# Control.net
KiCad netlist of a schematic drawn in Altium Designer
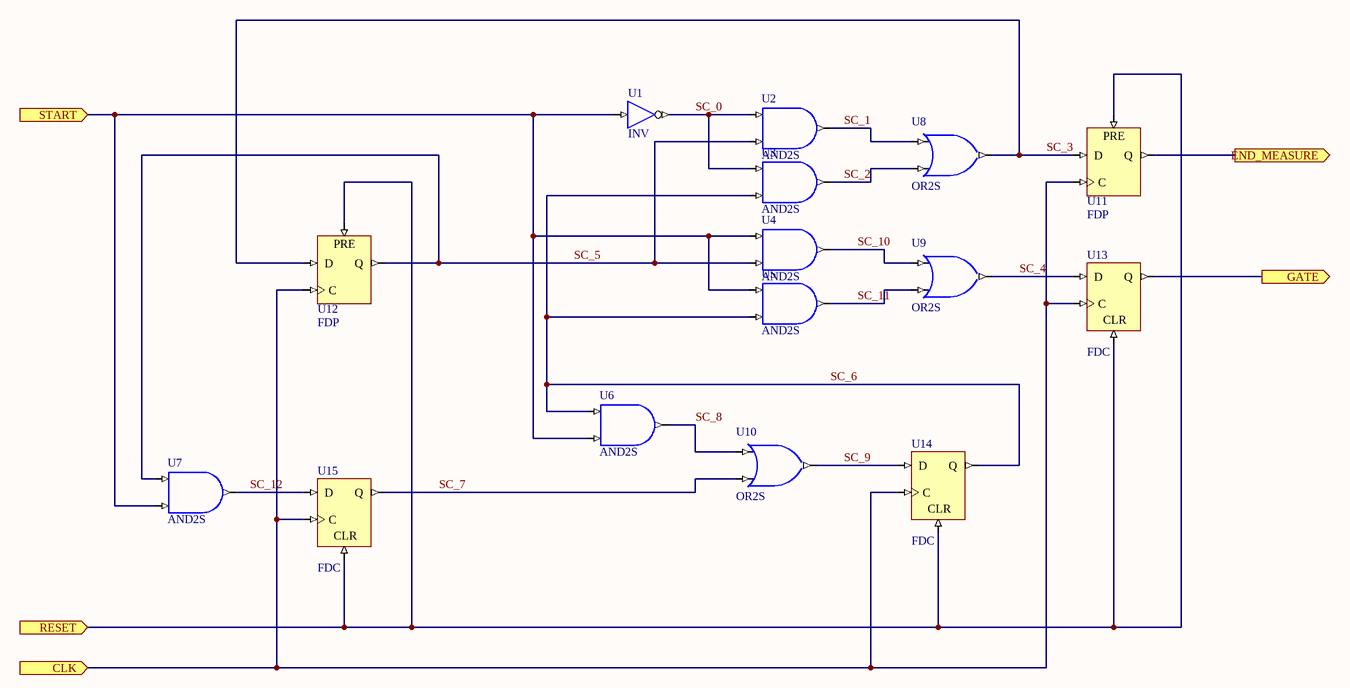
[diagram p0: Control.SchDoc]

(export (version "E")
  (design (tool "Eeschema 10.0.6"))
  (components
    (comp (ref "U1")
      (value "INV")
      (description "Inverter")
      (fields (field (name "PUBLISHER") "Altium Limited"))
      (libsource (lib "FPGA Generic") (part "INV"))
    )
    (comp (ref "U2")
      (value "AND2S")
      (description "2-Input AND Gate, Single Pin Version")
      (fields (field (name "PUBLISHER") "Altium Limited"))
      (libsource (lib "FPGA Generic") (part "AND2S"))
    )
    (comp (ref "U3")
      (value "AND2S")
      (description "2-Input AND Gate, Single Pin Version")
      (fields (field (name "PUBLISHER") "Altium Limited"))
      (libsource (lib "FPGA Generic") (part "AND2S"))
    )
    (comp (ref "U4")
      (value "AND2S")
      (description "2-Input AND Gate, Single Pin Version")
      (fields (field (name "PUBLISHER") "Altium Limited"))
      (libsource (lib "FPGA Generic") (part "AND2S"))
    )
    (comp (ref "U5")
      (value "AND2S")
      (description "2-Input AND Gate, Single Pin Version")
      (fields (field (name "PUBLISHER") "Altium Limited"))
      (libsource (lib "FPGA Generic") (part "AND2S"))
    )
    (comp (ref "U6")
      (value "AND2S")
      (description "2-Input AND Gate, Single Pin Version")
      (fields (field (name "PUBLISHER") "Altium Limited"))
      (libsource (lib "FPGA Generic") (part "AND2S"))
    )
    (comp (ref "U7")
      (value "AND2S")
      (description "2-Input AND Gate, Single Pin Version")
      (fields (field (name "PUBLISHER") "Altium Limited"))
      (libsource (lib "FPGA Generic") (part "AND2S"))
    )
    (comp (ref "U8")
      (value "OR2S")
      (description "2-Input OR Gate, Single Pin Version")
      (fields (field (name "PUBLISHER") "Altium Limited"))
      (libsource (lib "FPGA Generic") (part "OR2S"))
    )
    (comp (ref "U9")
      (value "OR2S")
      (description "2-Input OR Gate, Single Pin Version")
      (fields (field (name "PUBLISHER") "Altium Limited"))
      (libsource (lib "FPGA Generic") (part "OR2S"))
    )
    (comp (ref "U10")
      (value "OR2S")
      (description "2-Input OR Gate, Single Pin Version")
      (fields (field (name "PUBLISHER") "Altium Limited"))
      (libsource (lib "FPGA Generic") (part "OR2S"))
    )
    (comp (ref "U11")
      (value "FDP")
      (description "D-Type Flip-Flop with Asynchronous Preset")
      (fields (field (name "PUBLISHER") "Altium Limited"))
      (libsource (lib "FPGA Generic") (part "FDP"))
    )
    (comp (ref "U12")
      (value "FDP")
      (description "D-Type Flip-Flop with Asynchronous Preset")
      (fields (field (name "PUBLISHER") "Altium Limited"))
      (libsource (lib "FPGA Generic") (part "FDP"))
    )
    (comp (ref "U13")
      (value "FDC")
      (description "D-Type Flip-Flop with Asynchronous Clear")
      (fields (field (name "PUBLISHER") "Altium Limited"))
      (libsource (lib "FPGA Generic") (part "FDC"))
    )
    (comp (ref "U14")
      (value "FDC")
      (description "D-Type Flip-Flop with Asynchronous Clear")
      (fields (field (name "PUBLISHER") "Altium Limited"))
      (libsource (lib "FPGA Generic") (part "FDC"))
    )
    (comp (ref "U15")
      (value "FDC")
      (description "D-Type Flip-Flop with Asynchronous Clear")
      (fields (field (name "PUBLISHER") "Altium Limited"))
      (libsource (lib "FPGA Generic") (part "FDC"))
    )
  )
  (nets
    (net (code "1") (name "/CLK") (class "Default")
      (node (ref "U11") (pin "C") (pinfunction "C_C") (pintype "input"))
      (node (ref "U12") (pin "C") (pinfunction "C_C") (pintype "input"))
      (node (ref "U13") (pin "C") (pinfunction "C_C") (pintype "input"))
      (node (ref "U14") (pin "C") (pinfunction "C_C") (pintype "input"))
      (node (ref "U15") (pin "C") (pinfunction "C_C") (pintype "input"))
    )
    (net (code "2") (name "/END_MEASURE") (class "Default")
      (node (ref "U11") (pin "Q") (pinfunction "Q_Q") (pintype "output"))
    )
    (net (code "3") (name "/GATE") (class "Default")
      (node (ref "U13") (pin "Q") (pinfunction "Q_Q") (pintype "output"))
    )
    (net (code "4") (name "/RESET") (class "Default")
      (node (ref "U11") (pin "PRE") (pinfunction "PRE_PRE") (pintype "input"))
      (node (ref "U12") (pin "PRE") (pinfunction "PRE_PRE") (pintype "input"))
      (node (ref "U13") (pin "CLR") (pinfunction "CLR_CLR") (pintype "input"))
      (node (ref "U14") (pin "CLR") (pinfunction "CLR_CLR") (pintype "input"))
      (node (ref "U15") (pin "CLR") (pinfunction "CLR_CLR") (pintype "input"))
    )
    (net (code "5") (name "/SC_0") (class "Default")
      (node (ref "U1") (pin "O") (pinfunction "O_O") (pintype "output"))
      (node (ref "U2") (pin "I0") (pinfunction "I0_I0") (pintype "input"))
      (node (ref "U3") (pin "I0") (pinfunction "I0_I0") (pintype "input"))
    )
    (net (code "6") (name "/SC_1") (class "Default")
      (node (ref "U2") (pin "O") (pinfunction "O_O") (pintype "output"))
      (node (ref "U8") (pin "I0") (pinfunction "I0_I0") (pintype "input"))
    )
    (net (code "7") (name "/SC_2") (class "Default")
      (node (ref "U3") (pin "O") (pinfunction "O_O") (pintype "output"))
      (node (ref "U8") (pin "I1") (pinfunction "I1_I1") (pintype "input"))
    )
    (net (code "8") (name "/SC_3") (class "Default")
      (node (ref "U11") (pin "D") (pinfunction "D_D") (pintype "input"))
      (node (ref "U12") (pin "D") (pinfunction "D_D") (pintype "input"))
      (node (ref "U8") (pin "O") (pinfunction "O_O") (pintype "output"))
    )
    (net (code "9") (name "/SC_4") (class "Default")
      (node (ref "U13") (pin "D") (pinfunction "D_D") (pintype "input"))
      (node (ref "U9") (pin "O") (pinfunction "O_O") (pintype "output"))
    )
    (net (code "10") (name "/SC_5") (class "Default")
      (node (ref "U12") (pin "Q") (pinfunction "Q_Q") (pintype "output"))
      (node (ref "U2") (pin "I1") (pinfunction "I1_I1") (pintype "input"))
      (node (ref "U4") (pin "I1") (pinfunction "I1_I1") (pintype "input"))
      (node (ref "U7") (pin "I0") (pinfunction "I0_I0") (pintype "input"))
    )
    (net (code "11") (name "/SC_6") (class "Default")
      (node (ref "U14") (pin "Q") (pinfunction "Q_Q") (pintype "output"))
      (node (ref "U3") (pin "I1") (pinfunction "I1_I1") (pintype "input"))
      (node (ref "U5") (pin "I1") (pinfunction "I1_I1") (pintype "input"))
      (node (ref "U6") (pin "I0") (pinfunction "I0_I0") (pintype "input"))
    )
    (net (code "12") (name "/SC_7") (class "Default")
      (node (ref "U10") (pin "I1") (pinfunction "I1_I1") (pintype "input"))
      (node (ref "U15") (pin "Q") (pinfunction "Q_Q") (pintype "output"))
    )
    (net (code "13") (name "/SC_8") (class "Default")
      (node (ref "U10") (pin "I0") (pinfunction "I0_I0") (pintype "input"))
      (node (ref "U6") (pin "O") (pinfunction "O_O") (pintype "output"))
    )
    (net (code "14") (name "/SC_9") (class "Default")
      (node (ref "U10") (pin "O") (pinfunction "O_O") (pintype "output"))
      (node (ref "U14") (pin "D") (pinfunction "D_D") (pintype "input"))
    )
    (net (code "15") (name "/SC_10") (class "Default")
      (node (ref "U4") (pin "O") (pinfunction "O_O") (pintype "output"))
      (node (ref "U9") (pin "I0") (pinfunction "I0_I0") (pintype "input"))
    )
    (net (code "16") (name "/SC_11") (class "Default")
      (node (ref "U5") (pin "O") (pinfunction "O_O") (pintype "output"))
      (node (ref "U9") (pin "I1") (pinfunction "I1_I1") (pintype "input"))
    )
    (net (code "17") (name "/SC_12") (class "Default")
      (node (ref "U15") (pin "D") (pinfunction "D_D") (pintype "input"))
      (node (ref "U7") (pin "O") (pinfunction "O_O") (pintype "output"))
    )
    (net (code "18") (name "/START") (class "Default")
      (node (ref "U1") (pin "I") (pinfunction "I_I") (pintype "input"))
      (node (ref "U4") (pin "I0") (pinfunction "I0_I0") (pintype "input"))
      (node (ref "U5") (pin "I0") (pinfunction "I0_I0") (pintype "input"))
      (node (ref "U6") (pin "I1") (pinfunction "I1_I1") (pintype "input"))
      (node (ref "U7") (pin "I1") (pinfunction "I1_I1") (pintype "input"))
    )
  )
)
